# SUM_1_0.net
KiCad netlist of a schematic drawn in EAGLE
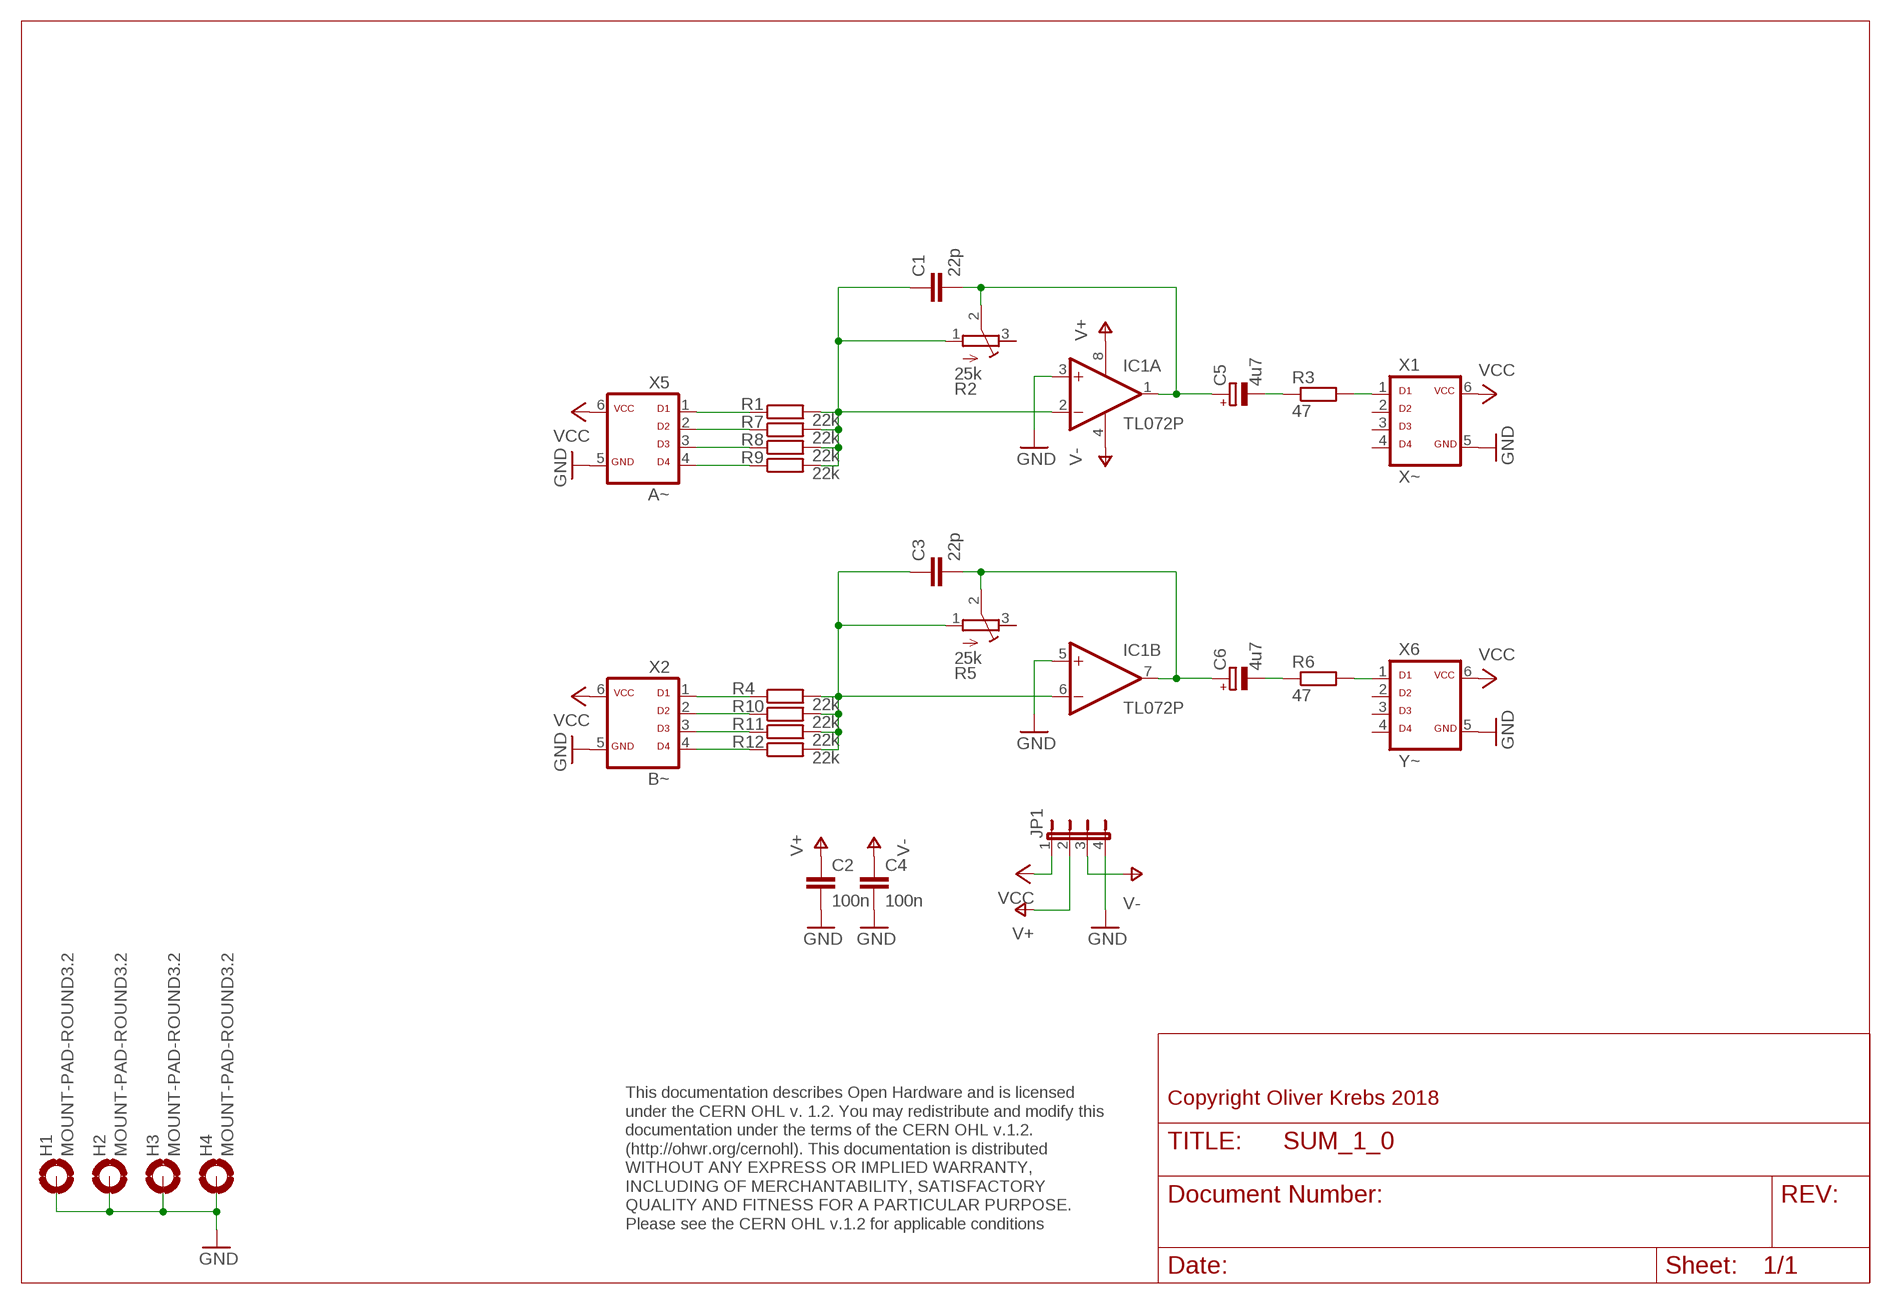
[diagram p0: schematic, sheet 1]

(export (version "E")
  (design (tool "Eeschema 10.0.6"))
  (components
    (comp (ref "C1")
      (value "22p")
      (footprint "eagle-import:C050-025X075")
      (libsource (lib "eagle-import") (part "C-EU050-025X075"))
    )
    (comp (ref "C2")
      (value "100n")
      (footprint "eagle-import:C050-025X075")
      (libsource (lib "eagle-import") (part "C-EU050-025X075"))
    )
    (comp (ref "C3")
      (value "22p")
      (footprint "eagle-import:C050-025X075")
      (libsource (lib "eagle-import") (part "C-EU050-025X075"))
    )
    (comp (ref "C4")
      (value "100n")
      (footprint "eagle-import:C050-025X075")
      (libsource (lib "eagle-import") (part "C-EU050-025X075"))
    )
    (comp (ref "C5")
      (value "4u7")
      (footprint "eagle-import:E2-4")
      (libsource (lib "eagle-import") (part "CPOL-EUE2-4"))
    )
    (comp (ref "C6")
      (value "4u7")
      (footprint "eagle-import:E2-4")
      (libsource (lib "eagle-import") (part "CPOL-EUE2-4"))
    )
    (comp (ref "H1")
      (value "MOUNT-PAD-ROUND3.2")
      (footprint "eagle-import:3,2-PAD")
      (libsource (lib "eagle-import") (part "MOUNT-PAD-ROUND3.2"))
    )
    (comp (ref "H2")
      (value "MOUNT-PAD-ROUND3.2")
      (footprint "eagle-import:3,2-PAD")
      (libsource (lib "eagle-import") (part "MOUNT-PAD-ROUND3.2"))
    )
    (comp (ref "H3")
      (value "MOUNT-PAD-ROUND3.2")
      (footprint "eagle-import:3,2-PAD")
      (libsource (lib "eagle-import") (part "MOUNT-PAD-ROUND3.2"))
    )
    (comp (ref "H4")
      (value "MOUNT-PAD-ROUND3.2")
      (footprint "eagle-import:3,2-PAD")
      (libsource (lib "eagle-import") (part "MOUNT-PAD-ROUND3.2"))
    )
    (comp (ref "IC1")
      (value "TL072P")
      (footprint "eagle-import:DIL08")
      (libsource (lib "eagle-import") (part "TL072P"))
    )
    (comp (ref "JP1")
      (value "JP4E")
      (footprint "eagle-import:JP4")
      (libsource (lib "eagle-import") (part "JP4E"))
    )
    (comp (ref "R1")
      (value "22k")
      (footprint "eagle-import:0207_10")
      (libsource (lib "eagle-import") (part "R-EU_0207/10"))
    )
    (comp (ref "R2")
      (value "25k")
      (footprint "eagle-import:ACP-6L")
      (libsource (lib "eagle-import") (part "R-TRIMMACP"))
    )
    (comp (ref "R3")
      (value "47")
      (footprint "eagle-import:0207_10")
      (libsource (lib "eagle-import") (part "R-EU_0207/10"))
    )
    (comp (ref "R4")
      (value "22k")
      (footprint "eagle-import:0207_10")
      (libsource (lib "eagle-import") (part "R-EU_0207/10"))
    )
    (comp (ref "R5")
      (value "25k")
      (footprint "eagle-import:ACP-6L")
      (libsource (lib "eagle-import") (part "R-TRIMMACP"))
    )
    (comp (ref "R6")
      (value "47")
      (footprint "eagle-import:0207_10")
      (libsource (lib "eagle-import") (part "R-EU_0207/10"))
    )
    (comp (ref "R7")
      (value "22k")
      (footprint "eagle-import:0207_10")
      (libsource (lib "eagle-import") (part "R-EU_0207/10"))
    )
    (comp (ref "R8")
      (value "22k")
      (footprint "eagle-import:0207_10")
      (libsource (lib "eagle-import") (part "R-EU_0207/10"))
    )
    (comp (ref "R9")
      (value "22k")
      (footprint "eagle-import:0207_10")
      (libsource (lib "eagle-import") (part "R-EU_0207/10"))
    )
    (comp (ref "R10")
      (value "22k")
      (footprint "eagle-import:0207_10")
      (libsource (lib "eagle-import") (part "R-EU_0207/10"))
    )
    (comp (ref "R11")
      (value "22k")
      (footprint "eagle-import:0207_10")
      (libsource (lib "eagle-import") (part "R-EU_0207/10"))
    )
    (comp (ref "R12")
      (value "22k")
      (footprint "eagle-import:0207_10")
      (libsource (lib "eagle-import") (part "R-EU_0207/10"))
    )
    (comp (ref "X1")
      (value "X~")
      (footprint "eagle-import:ML-6")
      (libsource (lib "eagle-import") (part "ML6D"))
    )
    (comp (ref "X2")
      (value "B~")
      (footprint "eagle-import:ML-6")
      (libsource (lib "eagle-import") (part "ML6D"))
    )
    (comp (ref "X5")
      (value "A~")
      (footprint "eagle-import:ML-6")
      (libsource (lib "eagle-import") (part "ML6D"))
    )
    (comp (ref "X6")
      (value "Y~")
      (footprint "eagle-import:ML-6")
      (libsource (lib "eagle-import") (part "ML6D"))
    )
  )
  (nets
    (net (code "1") (name "GND") (class "Default")
      (node (ref "C2") (pin "2") (pinfunction "2_2") (pintype "passive"))
      (node (ref "C4") (pin "2") (pinfunction "2_2") (pintype "passive"))
      (node (ref "H1") (pin "B3,2") (pinfunction "MOUNT_B3,2") (pintype "passive"))
      (node (ref "H2") (pin "B3,2") (pinfunction "MOUNT_B3,2") (pintype "passive"))
      (node (ref "H3") (pin "B3,2") (pinfunction "MOUNT_B3,2") (pintype "passive"))
      (node (ref "H4") (pin "B3,2") (pinfunction "MOUNT_B3,2") (pintype "passive"))
      (node (ref "IC1") (pin "3") (pinfunction "+IN_3") (pintype "input"))
      (node (ref "IC1") (pin "5") (pinfunction "+IN_5") (pintype "input"))
      (node (ref "JP1") (pin "4") (pinfunction "4_4") (pintype "passive"))
      (node (ref "X1") (pin "5") (pinfunction "5_5") (pintype "passive"))
      (node (ref "X2") (pin "5") (pinfunction "5_5") (pintype "passive"))
      (node (ref "X5") (pin "5") (pinfunction "5_5") (pintype "passive"))
      (node (ref "X6") (pin "5") (pinfunction "5_5") (pintype "passive"))
    )
    (net (code "2") (name "Net-(C5-Pad-)") (class "Default")
      (node (ref "C5") (pin "-") (pinfunction "-_-") (pintype "passive"))
      (node (ref "R3") (pin "1") (pinfunction "1_1") (pintype "passive"))
    )
    (net (code "3") (name "Net-(C6-Pad-)") (class "Default")
      (node (ref "C6") (pin "-") (pinfunction "-_-") (pintype "passive"))
      (node (ref "R6") (pin "1") (pinfunction "1_1") (pintype "passive"))
    )
    (net (code "4") (name "Net-(IC1A--IN)") (class "Default")
      (node (ref "C1") (pin "1") (pinfunction "1_1") (pintype "passive"))
      (node (ref "IC1") (pin "2") (pinfunction "-IN_2") (pintype "input"))
      (node (ref "R1") (pin "2") (pinfunction "2_2") (pintype "passive"))
      (node (ref "R2") (pin "1") (pinfunction "A_1") (pintype "passive"))
      (node (ref "R7") (pin "2") (pinfunction "2_2") (pintype "passive"))
      (node (ref "R8") (pin "2") (pinfunction "2_2") (pintype "passive"))
      (node (ref "R9") (pin "2") (pinfunction "2_2") (pintype "passive"))
    )
    (net (code "5") (name "Net-(IC1A-OUT)") (class "Default")
      (node (ref "C1") (pin "2") (pinfunction "2_2") (pintype "passive"))
      (node (ref "C5") (pin "+") (pinfunction "+_+") (pintype "passive"))
      (node (ref "IC1") (pin "1") (pinfunction "OUT_1") (pintype "output"))
      (node (ref "R2") (pin "2") (pinfunction "S_2") (pintype "passive"))
    )
    (net (code "6") (name "Net-(IC1B--IN)") (class "Default")
      (node (ref "C3") (pin "1") (pinfunction "1_1") (pintype "passive"))
      (node (ref "IC1") (pin "6") (pinfunction "-IN_6") (pintype "input"))
      (node (ref "R10") (pin "2") (pinfunction "2_2") (pintype "passive"))
      (node (ref "R11") (pin "2") (pinfunction "2_2") (pintype "passive"))
      (node (ref "R12") (pin "2") (pinfunction "2_2") (pintype "passive"))
      (node (ref "R4") (pin "2") (pinfunction "2_2") (pintype "passive"))
      (node (ref "R5") (pin "1") (pinfunction "A_1") (pintype "passive"))
    )
    (net (code "7") (name "Net-(IC1B-OUT)") (class "Default")
      (node (ref "C3") (pin "2") (pinfunction "2_2") (pintype "passive"))
      (node (ref "C6") (pin "+") (pinfunction "+_+") (pintype "passive"))
      (node (ref "IC1") (pin "7") (pinfunction "OUT_7") (pintype "output"))
      (node (ref "R5") (pin "2") (pinfunction "S_2") (pintype "passive"))
    )
    (net (code "8") (name "Net-(R1-Pad1)") (class "Default")
      (node (ref "R1") (pin "1") (pinfunction "1_1") (pintype "passive"))
      (node (ref "X5") (pin "1") (pinfunction "1_1") (pintype "passive"))
    )
    (net (code "9") (name "Net-(R3-Pad2)") (class "Default")
      (node (ref "R3") (pin "2") (pinfunction "2_2") (pintype "passive"))
      (node (ref "X1") (pin "1") (pinfunction "1_1") (pintype "passive"))
    )
    (net (code "10") (name "Net-(R4-Pad1)") (class "Default")
      (node (ref "R4") (pin "1") (pinfunction "1_1") (pintype "passive"))
      (node (ref "X2") (pin "1") (pinfunction "1_1") (pintype "passive"))
    )
    (net (code "11") (name "Net-(R6-Pad2)") (class "Default")
      (node (ref "R6") (pin "2") (pinfunction "2_2") (pintype "passive"))
      (node (ref "X6") (pin "1") (pinfunction "1_1") (pintype "passive"))
    )
    (net (code "12") (name "Net-(R7-Pad1)") (class "Default")
      (node (ref "R7") (pin "1") (pinfunction "1_1") (pintype "passive"))
      (node (ref "X5") (pin "2") (pinfunction "2_2") (pintype "passive"))
    )
    (net (code "13") (name "Net-(R8-Pad1)") (class "Default")
      (node (ref "R8") (pin "1") (pinfunction "1_1") (pintype "passive"))
      (node (ref "X5") (pin "3") (pinfunction "3_3") (pintype "passive"))
    )
    (net (code "14") (name "Net-(R9-Pad1)") (class "Default")
      (node (ref "R9") (pin "1") (pinfunction "1_1") (pintype "passive"))
      (node (ref "X5") (pin "4") (pinfunction "4_4") (pintype "passive"))
    )
    (net (code "15") (name "Net-(R10-Pad1)") (class "Default")
      (node (ref "R10") (pin "1") (pinfunction "1_1") (pintype "passive"))
      (node (ref "X2") (pin "2") (pinfunction "2_2") (pintype "passive"))
    )
    (net (code "16") (name "Net-(R11-Pad1)") (class "Default")
      (node (ref "R11") (pin "1") (pinfunction "1_1") (pintype "passive"))
      (node (ref "X2") (pin "3") (pinfunction "3_3") (pintype "passive"))
    )
    (net (code "17") (name "Net-(R12-Pad1)") (class "Default")
      (node (ref "R12") (pin "1") (pinfunction "1_1") (pintype "passive"))
      (node (ref "X2") (pin "4") (pinfunction "4_4") (pintype "passive"))
    )
    (net (code "18") (name "V+") (class "Default")
      (node (ref "C2") (pin "1") (pinfunction "1_1") (pintype "passive"))
      (node (ref "IC1") (pin "8") (pinfunction "V+_8") (pintype "power_in"))
      (node (ref "JP1") (pin "2") (pinfunction "2_2") (pintype "passive"))
    )
    (net (code "19") (name "V-") (class "Default")
      (node (ref "C4") (pin "1") (pinfunction "1_1") (pintype "passive"))
      (node (ref "IC1") (pin "4") (pinfunction "V-_4") (pintype "power_in"))
      (node (ref "JP1") (pin "3") (pinfunction "3_3") (pintype "passive"))
    )
    (net (code "20") (name "VCC") (class "Default")
      (node (ref "JP1") (pin "1") (pinfunction "1_1") (pintype "passive"))
      (node (ref "X1") (pin "6") (pinfunction "6_6") (pintype "passive"))
      (node (ref "X2") (pin "6") (pinfunction "6_6") (pintype "passive"))
      (node (ref "X5") (pin "6") (pinfunction "6_6") (pintype "passive"))
      (node (ref "X6") (pin "6") (pinfunction "6_6") (pintype "passive"))
    )
    (net (code "21") (name "unconnected-(R2-E-Pad3)") (class "Default")
      (node (ref "R2") (pin "3") (pinfunction "E_3") (pintype "passive"))
    )
    (net (code "22") (name "unconnected-(R5-E-Pad3)") (class "Default")
      (node (ref "R5") (pin "3") (pinfunction "E_3") (pintype "passive"))
    )
    (net (code "23") (name "unconnected-(X1-Pad2)") (class "Default")
      (node (ref "X1") (pin "2") (pinfunction "2_2") (pintype "passive"))
    )
    (net (code "24") (name "unconnected-(X1-Pad3)") (class "Default")
      (node (ref "X1") (pin "3") (pinfunction "3_3") (pintype "passive"))
    )
    (net (code "25") (name "unconnected-(X1-Pad4)") (class "Default")
      (node (ref "X1") (pin "4") (pinfunction "4_4") (pintype "passive"))
    )
    (net (code "26") (name "unconnected-(X6-Pad2)") (class "Default")
      (node (ref "X6") (pin "2") (pinfunction "2_2") (pintype "passive"))
    )
    (net (code "27") (name "unconnected-(X6-Pad3)") (class "Default")
      (node (ref "X6") (pin "3") (pinfunction "3_3") (pintype "passive"))
    )
    (net (code "28") (name "unconnected-(X6-Pad4)") (class "Default")
      (node (ref "X6") (pin "4") (pinfunction "4_4") (pintype "passive"))
    )
  )
)
